# channel_3.net
KiCad netlist of a schematic drawn in Altium Designer
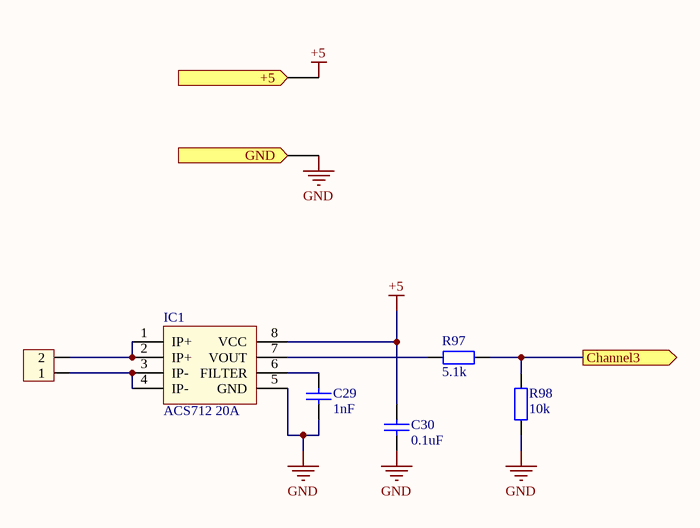
[diagram p0: channel_3.SchDoc]

(export (version "E")
  (design (tool "Eeschema 10.0.6"))
  (components
    (comp (ref "C29")
      (value "1nF")
      (footprint "tu 0603")
      (description "Dán")
      (libsource (lib "TrungVan_Lib") (part "Tu 0603 105 16V 20%"))
    )
    (comp (ref "C30")
      (value "0.1uF")
      (footprint "tu 0603")
      (description "Dán")
      (libsource (lib "TrungVan_Lib") (part "Tu 0603 105 16V 20%"))
    )
    (comp (ref "H3")
      (value "Header 2P 2.54 Duc Thang")
      (footprint "15EDGR-3.81-2P")
      (description "Cắm")
      (libsource (lib "TrungVan_Lib") (part "Header 2P 2.54 Duc Thang"))
    )
    (comp (ref "IC1")
      (value "ACS712 20A")
      (footprint "sop8")
      (description "Cắm")
      (libsource (lib "TrungVan_Lib") (part "ACS712"))
    )
    (comp (ref "R97")
      (value "5.1k")
      (footprint "tro smd 0805")
      (description "Dán")
      (libsource (lib "TrungVan_Lib") (part "Tro 0603 1% 10k"))
    )
    (comp (ref "R98")
      (value "10k")
      (footprint "tro smd 0805")
      (description "Dán")
      (libsource (lib "TrungVan_Lib") (part "Tro 0603 1% 10k"))
    )
  )
  (nets
    (net (code "1") (name "+5") (class "Default")
      (node (ref "C30") (pin "1") (pinfunction "1_1") (pintype "passive"))
      (node (ref "IC1") (pin "8") (pinfunction "VCC_8") (pintype "passive"))
    )
    (net (code "2") (name "/Channel3") (class "Default")
      (node (ref "R97") (pin "2") (pinfunction "2_2") (pintype "passive"))
      (node (ref "R98") (pin "2") (pinfunction "2_2") (pintype "passive"))
    )
    (net (code "3") (name "GND") (class "Default")
      (node (ref "C29") (pin "2") (pinfunction "2_2") (pintype "passive"))
      (node (ref "C30") (pin "2") (pinfunction "2_2") (pintype "passive"))
      (node (ref "IC1") (pin "5") (pinfunction "GND_5") (pintype "passive"))
      (node (ref "R98") (pin "1") (pinfunction "1_1") (pintype "passive"))
    )
    (net (code "4") (name "Net-(H3-Pad1)") (class "Default")
      (node (ref "H3") (pin "1") (pinfunction "1_1") (pintype "passive"))
      (node (ref "IC1") (pin "3") (pinfunction "IP-_3") (pintype "passive"))
      (node (ref "IC1") (pin "4") (pinfunction "IP-_4") (pintype "power_in"))
    )
    (net (code "5") (name "Net-(H3-Pad2)") (class "Default")
      (node (ref "H3") (pin "2") (pinfunction "2_2") (pintype "passive"))
      (node (ref "IC1") (pin "1") (pinfunction "IP+_1") (pintype "passive"))
      (node (ref "IC1") (pin "2") (pinfunction "IP+_2") (pintype "passive"))
    )
    (net (code "6") (name "Net-(IC1-FILTER)") (class "Default")
      (node (ref "C29") (pin "1") (pinfunction "1_1") (pintype "passive"))
      (node (ref "IC1") (pin "6") (pinfunction "FILTER_6") (pintype "passive"))
    )
    (net (code "7") (name "Net-(IC1-VOUT)") (class "Default")
      (node (ref "IC1") (pin "7") (pinfunction "VOUT_7") (pintype "passive"))
      (node (ref "R97") (pin "1") (pinfunction "1_1") (pintype "passive"))
    )
  )
)
